# Power.net
KiCad netlist of a schematic drawn in Altium Designer
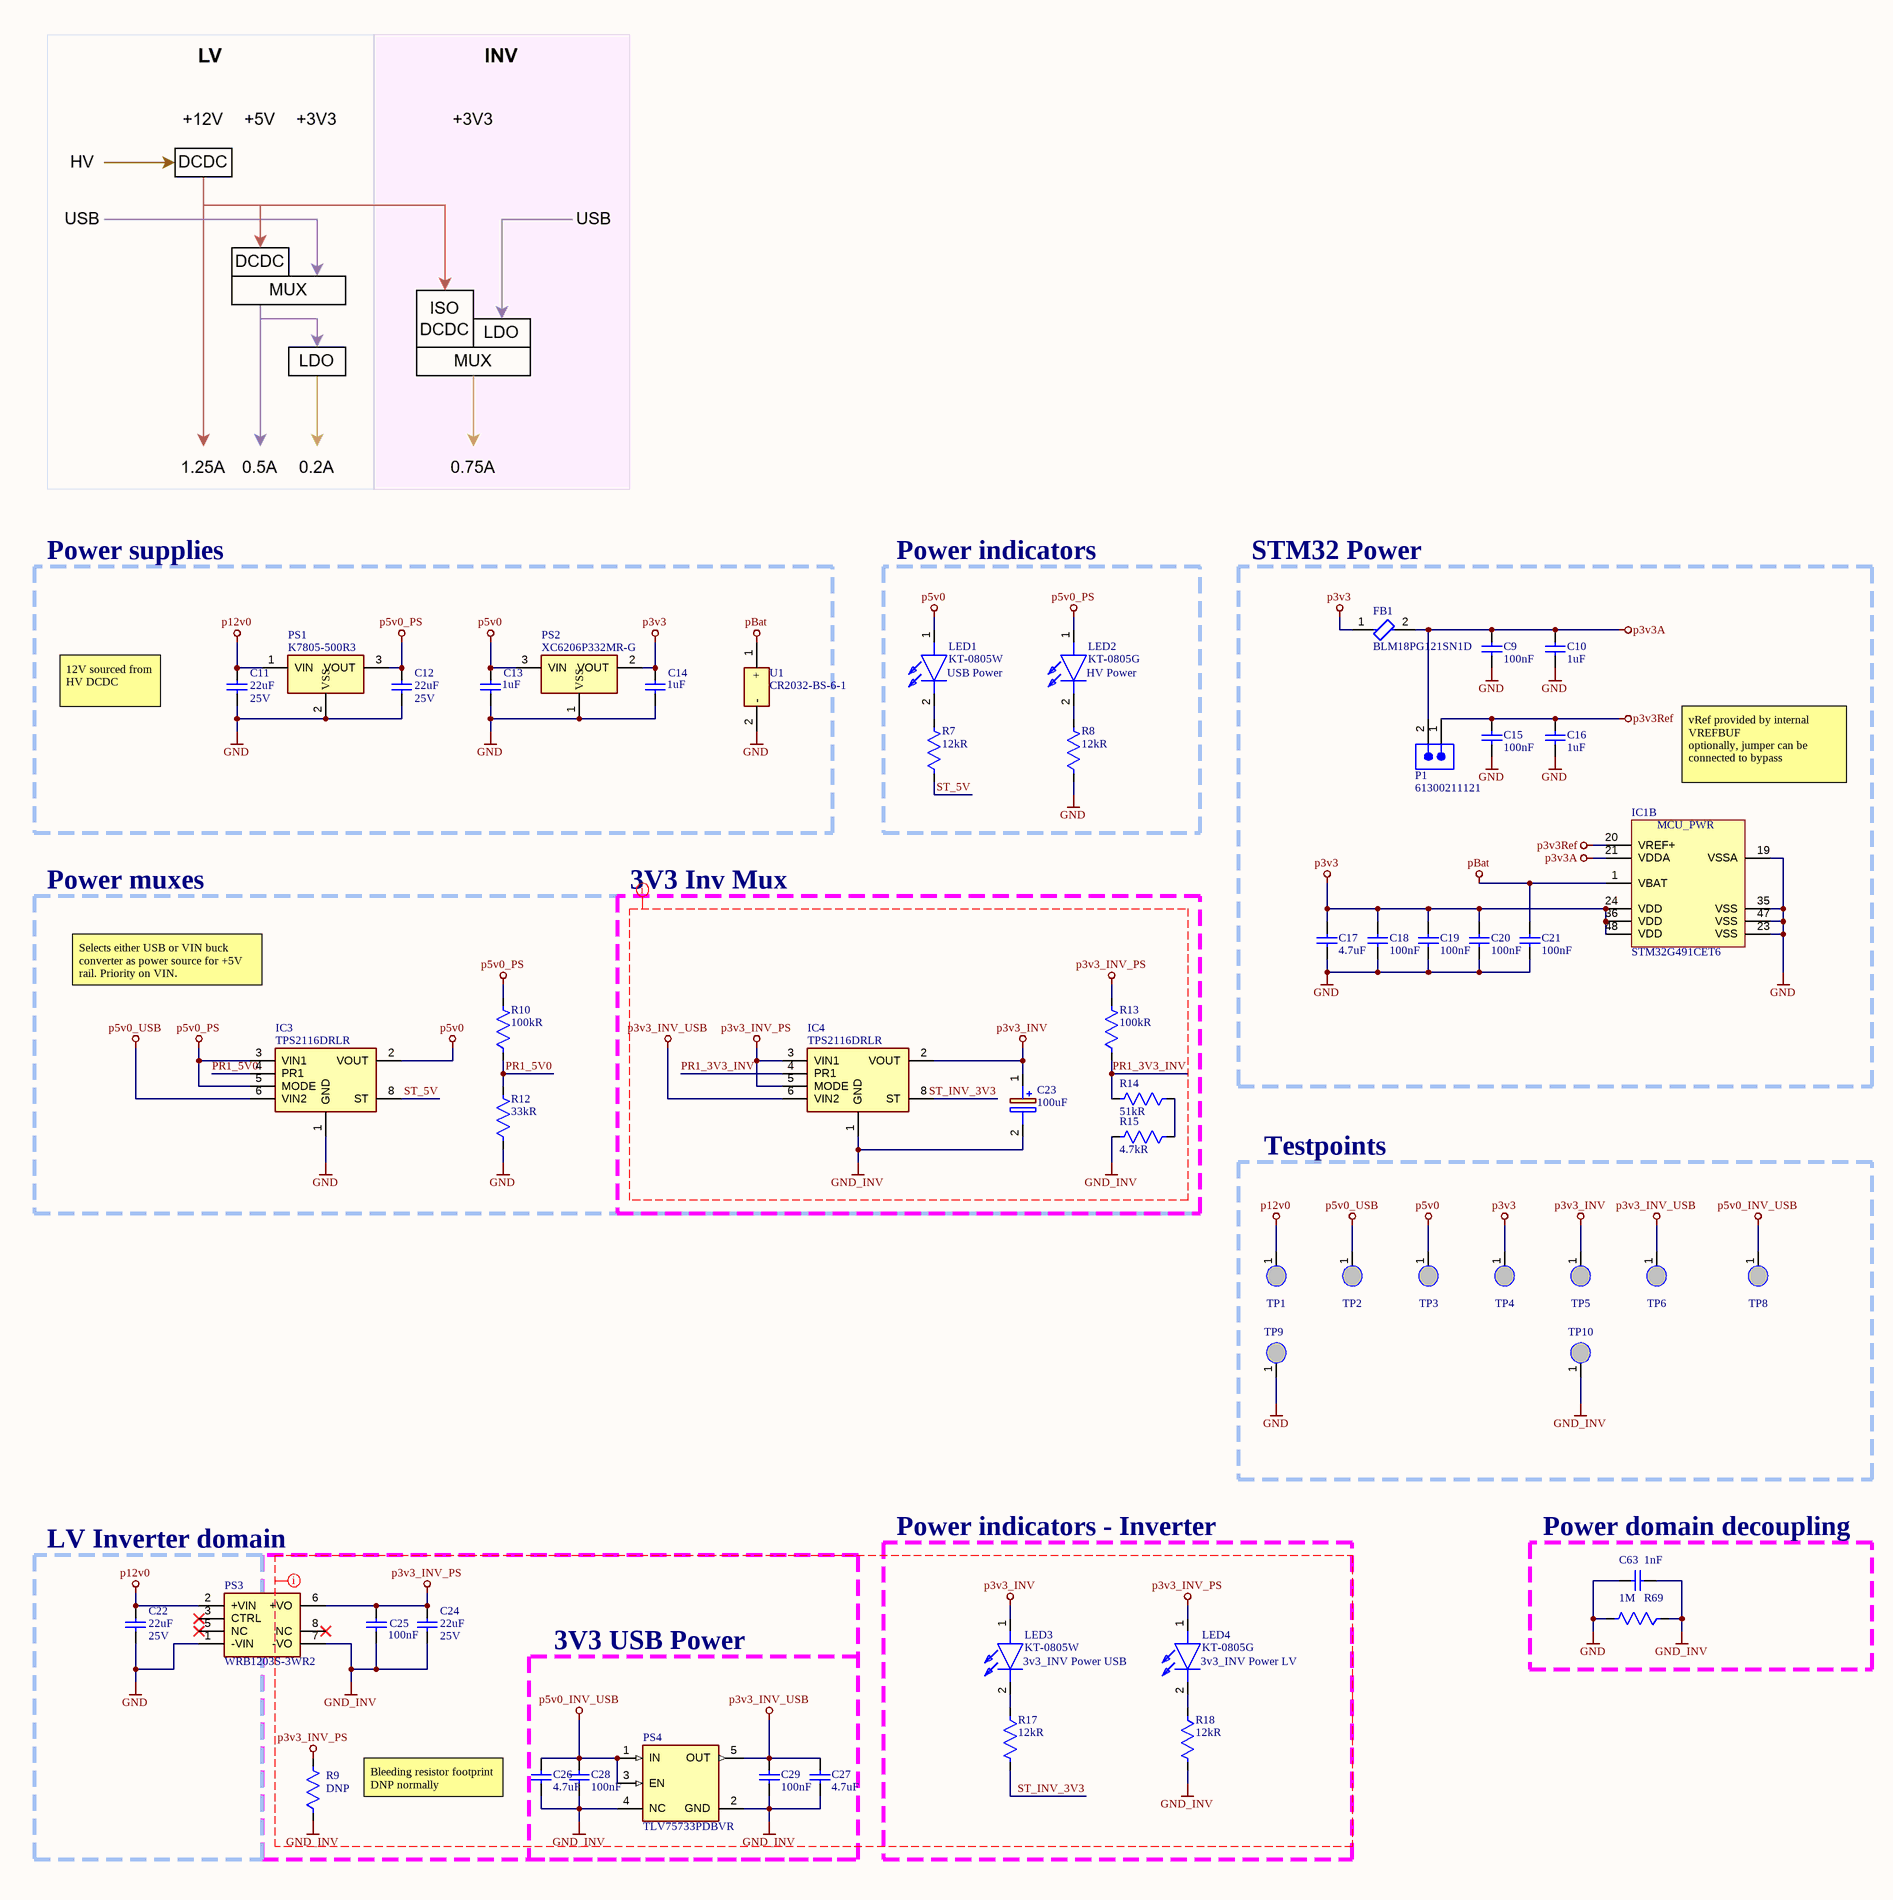
[diagram p0: Power.SchDoc, left]
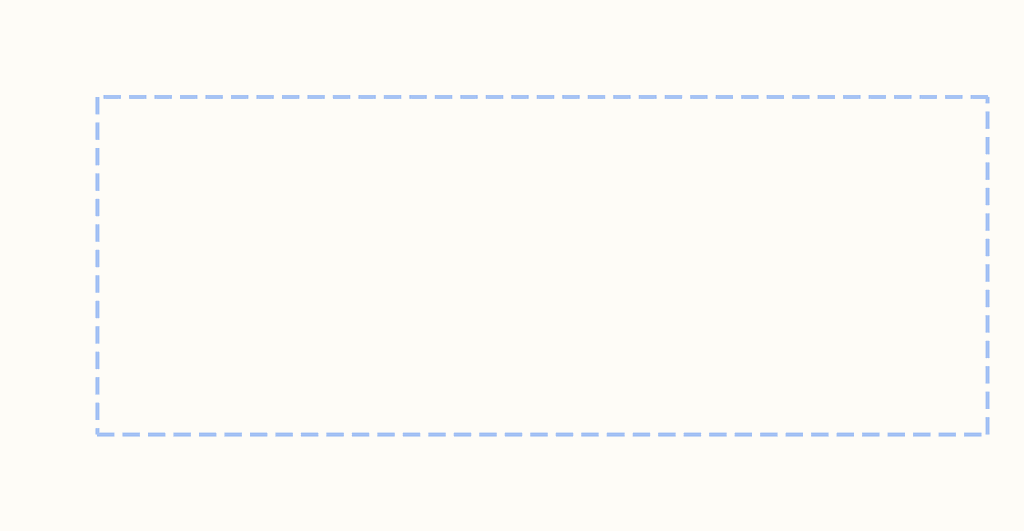
[diagram p1: Power.SchDoc, right]

(export (version "E")
  (design (tool "Eeschema 10.0.6"))
  (components
    (comp (ref "C9")
      (value "100nF")
      (footprint "WCAP-CSGP_0402_L1W0.5H0.5")
      (description "GTT Standard 0402 non-polarized capacitor")
      (fields (field (name "JLCPCB PART #") "C1525") (field (name "Comment") "CAP 0402 100nF X7R"))
      (libsource (lib "Green Team Twente") (part "CAP_NONPOL_GENERIC"))
    )
    (comp (ref "C10")
      (value "1uF")
      (footprint "WCAP-CSGP_0603_L1.6W0.8H0.8_Reflow")
      (description "GTT Standard 0603 non-polarized capacitor")
      (fields (field (name "JLCPCB PART #") "C15849") (field (name "Comment") "CAP 0603 1uF X7R"))
      (libsource (lib "Green Team Twente") (part "CAP_NONPOL_GENERIC"))
    )
    (comp (ref "C11")
      (value "22uF")
      (footprint "WCAP-CSGP_1206_L3.2W1.6H1.15")
      (description "GTT Standard 1206 non-polarized capacitor")
      (fields
        (field (name "VOLTAGE RATING") "25V")
        (field (name "JLCPCB PART #") "C12891")
        (field (name "Comment") "CAP 1206 22uF X7R")
      )
      (libsource (lib "Green Team Twente") (part "CAP_NONPOL_GENERIC"))
    )
    (comp (ref "C12")
      (value "22uF")
      (footprint "WCAP-CSGP_1206_L3.2W1.6H1.15")
      (description "GTT Standard 1206 non-polarized capacitor")
      (fields
        (field (name "VOLTAGE RATING") "25V")
        (field (name "JLCPCB PART #") "C12891")
        (field (name "Comment") "CAP 1206 22uF X7R")
      )
      (libsource (lib "Green Team Twente") (part "CAP_NONPOL_GENERIC"))
    )
    (comp (ref "C13")
      (value "1uF")
      (footprint "WCAP-CSGP_0603_L1.6W0.8H0.8_Reflow")
      (description "GTT Standard 0603 non-polarized capacitor")
      (fields (field (name "JLCPCB PART #") "C15849") (field (name "Comment") "CAP 0603 1uF X7R"))
      (libsource (lib "Green Team Twente") (part "CAP_NONPOL_GENERIC"))
    )
    (comp (ref "C14")
      (value "1uF")
      (footprint "WCAP-CSGP_0603_L1.6W0.8H0.8_Reflow")
      (description "GTT Standard 0603 non-polarized capacitor")
      (fields (field (name "JLCPCB PART #") "C15849") (field (name "Comment") "CAP 0603 1uF X7R"))
      (libsource (lib "Green Team Twente") (part "CAP_NONPOL_GENERIC"))
    )
    (comp (ref "C15")
      (value "100nF")
      (footprint "WCAP-CSGP_0402_L1W0.5H0.5")
      (description "GTT Standard 0402 non-polarized capacitor")
      (fields (field (name "JLCPCB PART #") "C1525") (field (name "Comment") "CAP 0402 100nF X7R"))
      (libsource (lib "Green Team Twente") (part "CAP_NONPOL_GENERIC"))
    )
    (comp (ref "C16")
      (value "1uF")
      (footprint "WCAP-CSGP_0603_L1.6W0.8H0.8_Reflow")
      (description "GTT Standard 0603 non-polarized capacitor")
      (fields (field (name "JLCPCB PART #") "C15849") (field (name "Comment") "CAP 0603 1uF X7R"))
      (libsource (lib "Green Team Twente") (part "CAP_NONPOL_GENERIC"))
    )
    (comp (ref "C17")
      (value "4.7uF")
      (footprint "WCAP-CSGP_0603_L1.6W0.8H0.8_Reflow")
      (description "GTT Standard 0603 non-polarized capacitor")
      (fields (field (name "JLCPCB PART #") "C19666") (field (name "Comment") "CAP 0603 4.7uF X7R"))
      (libsource (lib "Green Team Twente") (part "CAP_NONPOL_GENERIC"))
    )
    (comp (ref "C18")
      (value "100nF")
      (footprint "WCAP-CSGP_0402_L1W0.5H0.5")
      (description "GTT Standard 0402 non-polarized capacitor")
      (fields (field (name "JLCPCB PART #") "C1525") (field (name "Comment") "CAP 0402 100nF X7R"))
      (libsource (lib "Green Team Twente") (part "CAP_NONPOL_GENERIC"))
    )
    (comp (ref "C19")
      (value "100nF")
      (footprint "WCAP-CSGP_0402_L1W0.5H0.5")
      (description "GTT Standard 0402 non-polarized capacitor")
      (fields (field (name "JLCPCB PART #") "C1525") (field (name "Comment") "CAP 0402 100nF X7R"))
      (libsource (lib "Green Team Twente") (part "CAP_NONPOL_GENERIC"))
    )
    (comp (ref "C20")
      (value "100nF")
      (footprint "WCAP-CSGP_0402_L1W0.5H0.5")
      (description "GTT Standard 0402 non-polarized capacitor")
      (fields (field (name "JLCPCB PART #") "C1525") (field (name "Comment") "CAP 0402 100nF X7R"))
      (libsource (lib "Green Team Twente") (part "CAP_NONPOL_GENERIC"))
    )
    (comp (ref "C21")
      (value "100nF")
      (footprint "WCAP-CSGP_0402_L1W0.5H0.5")
      (description "GTT Standard 0402 non-polarized capacitor")
      (fields (field (name "JLCPCB PART #") "C1525") (field (name "Comment") "CAP 0402 100nF X7R"))
      (libsource (lib "Green Team Twente") (part "CAP_NONPOL_GENERIC"))
    )
    (comp (ref "C22")
      (value "22uF")
      (footprint "WCAP-CSGP_1206_L3.2W1.6H1.15")
      (description "GTT Standard 1206 non-polarized capacitor")
      (fields
        (field (name "VOLTAGE RATING") "25V")
        (field (name "JLCPCB PART #") "C12891")
        (field (name "Comment") "CAP 1206 22uF X7R")
      )
      (libsource (lib "Green Team Twente") (part "CAP_NONPOL_GENERIC"))
    )
    (comp (ref "C23")
      (value "100uF")
      (footprint "CAPAE660X800N")
      (description "Capacitor Polarised")
      (fields
        (field (name "MANUFACTURER_PART_NUMBER") "VEJ101M1ETR-0607")
        (field (name "JLCPCB PART #") "C176664")
      )
      (libsource (lib "FlexBMS_lib") (part "VEJ101M1ETR-0607"))
    )
    (comp (ref "C24")
      (value "22uF")
      (footprint "WCAP-CSGP_1206_L3.2W1.6H1.15")
      (description "GTT Standard 1206 non-polarized capacitor")
      (fields
        (field (name "VOLTAGE RATING") "25V")
        (field (name "JLCPCB PART #") "C12891")
        (field (name "Comment") "CAP 1206 22uF X7R")
      )
      (libsource (lib "Green Team Twente") (part "CAP_NONPOL_GENERIC"))
    )
    (comp (ref "C25")
      (value "100nF")
      (footprint "WCAP-CSGP_0402_L1W0.5H0.5")
      (description "GTT Standard 0402 non-polarized capacitor")
      (fields (field (name "JLCPCB PART #") "C1525") (field (name "Comment") "CAP 0402 100nF X7R"))
      (libsource (lib "Green Team Twente") (part "CAP_NONPOL_GENERIC"))
    )
    (comp (ref "C26")
      (value "4.7uF")
      (footprint "WCAP-CSGP_0603_L1.6W0.8H0.8_Reflow")
      (description "GTT Standard 0603 non-polarized capacitor")
      (fields (field (name "JLCPCB PART #") "C19666") (field (name "Comment") "CAP 0603 4.7uF X5R"))
      (libsource (lib "Green Team Twente") (part "CAP_NONPOL_GENERIC"))
    )
    (comp (ref "C27")
      (value "4.7uF")
      (footprint "WCAP-CSGP_0603_L1.6W0.8H0.8_Reflow")
      (description "GTT Standard 0603 non-polarized capacitor")
      (fields (field (name "JLCPCB PART #") "C19666") (field (name "Comment") "CAP 0603 4.7uF X5R"))
      (libsource (lib "Green Team Twente") (part "CAP_NONPOL_GENERIC"))
    )
    (comp (ref "C28")
      (value "100nF")
      (footprint "WCAP-CSGP_0402_L1W0.5H0.5")
      (description "GTT Standard 0402 non-polarized capacitor")
      (fields (field (name "JLCPCB PART #") "C1525") (field (name "Comment") "CAP 0402 100nF X7R"))
      (libsource (lib "Green Team Twente") (part "CAP_NONPOL_GENERIC"))
    )
    (comp (ref "C29")
      (value "100nF")
      (footprint "WCAP-CSGP_0402_L1W0.5H0.5")
      (description "GTT Standard 0402 non-polarized capacitor")
      (fields (field (name "JLCPCB PART #") "C1525") (field (name "Comment") "CAP 0402 100nF X7R"))
      (libsource (lib "Green Team Twente") (part "CAP_NONPOL_GENERIC"))
    )
    (comp (ref "C63")
      (value "1nF")
      (footprint "WCAP-CSGP_1206_L3.2W1.6H1.15")
      (description "GTT Standard 1206 non-polarized capacitor")
      (fields (field (name "JLCPCB PART #") "C9196") (field (name "Comment") "CAP 1206 1nF X7R"))
      (libsource (lib "Green Team Twente") (part "CAP_NONPOL_GENERIC"))
    )
    (comp (ref "FB1")
      (value "BLM18PG121SN1D")
      (footprint "FP-BLM18-0_15-t0_8-IPC_A")
      (description "Chip Ferrite Bead, 0603, 120Ω @ 100MHz, 0.05Ω, 25%, 2A")
      (fields (field (name "TOLERANCE") "25%"))
      (libsource (lib "Altium Content Vault") (part "5f30dd21d616792df468990f7003faa"))
    )
    (comp (ref "IC1")
      (value "STM32G491CET6")
      (footprint "QFP50P900X900X160-48N")
      (description "ARM Microcontrollers - MCU Mainstream Arm Cortex-M4+ MCU 170MHz with 512Kbytes of Flash memory")
      (fields (field (name "MOUSER PART NUMBER") "511-STM32G491CET6"))
      (libsource (lib "Green Team Twente") (part "STM32G491CET6"))
    )
    (comp (ref "IC3")
      (value "TPS2116DRLR")
      (footprint "SOTFL50P160X60-8N")
      (description "Power MUX")
      (fields (field (name "MOUSER PART NUMBER") "595-TPS2116DRLR"))
      (libsource (lib "Green Team Twente") (part "TPS2116DRLR"))
    )
    (comp (ref "IC4")
      (value "TPS2116DRLR")
      (footprint "SOTFL50P160X60-8N")
      (description "Power MUX")
      (fields (field (name "MOUSER PART NUMBER") "595-TPS2116DRLR"))
      (libsource (lib "Green Team Twente") (part "TPS2116DRLR"))
    )
    (comp (ref "LED1")
      (value "KT-0805W")
      (footprint "KT0805G")
      (description "LED")
      (fields (field (name "MANUFACTURER_PART_NUMBER") "KT-0805G") (field (name "JLCPCB PART #") "C34499"))
      (libsource (lib "FlexBMS_lib") (part "KT-0805G"))
    )
    (comp (ref "LED2")
      (value "KT-0805G")
      (footprint "KT0805G")
      (description "LED")
      (fields (field (name "JLCPCB PART #") "C2297"))
      (libsource (lib "FlexBMS_lib") (part "KT-0805G"))
    )
    (comp (ref "LED3")
      (value "KT-0805W")
      (footprint "KT0805G")
      (description "LED")
      (fields (field (name "MANUFACTURER_PART_NUMBER") "KT-0805G") (field (name "JLCPCB PART #") "C34499"))
      (libsource (lib "FlexBMS_lib") (part "KT-0805G"))
    )
    (comp (ref "LED4")
      (value "KT-0805G")
      (footprint "KT0805G")
      (description "LED")
      (fields (field (name "JLCPCB PART #") "C2297"))
      (libsource (lib "FlexBMS_lib") (part "KT-0805G"))
    )
    (comp (ref "P1")
      (value "61300211121")
      (footprint "61300211121")
      (description "WR-PHD Pin Header, THT, Vertical, pitch 2.54mm, 1 Row, 2P")
      (fields (field (name "MANUFACTURER") "Wurth Elektronik"))
      (libsource (lib "Green Team Twente") (part "62000211121"))
    )
    (comp (ref "PS1")
      (value "K7805-500R3")
      (footprint "K7805500R3")
      (description "Power Supply")
      (fields (field (name "JLCPCB PART #") "C19188491"))
      (libsource (lib "FlexBMS_lib") (part "K7805-500R3"))
    )
    (comp (ref "PS2")
      (value "XC6206P332MR-G")
      (footprint "SOT95P280X130-3N")
      (description "Power Supply")
      (fields (field (name "MOUSER PART NUMBER") "865-XC6206P332MR-G"))
      (libsource (lib "FlexBMS_lib") (part "XC6206P332MR-G"))
    )
    (comp (ref "PS3")
      (value "WRB1203S-3WR2")
      (footprint "WRB1203S3WR2")
      (description "Power Supply")
      (fields (field (name "JLCPCB PART #") "C22437321"))
      (libsource (lib "FlexBMS_lib") (part "WRB1203S-3WR2"))
    )
    (comp (ref "PS4")
      (value "TLV75733PDBVR")
      (footprint "FP-DBV0005A-MFG")
      (description "IC REG LINEAR 3.3V 1A SOT23-5")
      (fields
        (field (name "MANUFACTURER") "Texas Instruments")
        (field (name "OCTOPART") "https://octopart.com/tlv75733pdbvr-texas+instruments-91437073")
      )
      (libsource (lib "Altium Content Vault") (part "0cbbc1df71e5372cce39b1d408f1f92"))
    )
    (comp (ref "R7")
      (value "12kR")
      (footprint "FP0402")
      (description "GTT Standard 0402 Resistor")
      (fields (field (name "TOLERANCE") "1%") (field (name "POWER") "62.5mW"))
      (libsource (lib "Green Team Twente") (part "RES_GENERIC"))
    )
    (comp (ref "R8")
      (value "12kR")
      (footprint "FP0402")
      (description "GTT Standard 0402 Resistor")
      (fields (field (name "TOLERANCE") "1%") (field (name "POWER") "62.5mW"))
      (libsource (lib "Green Team Twente") (part "RES_GENERIC"))
    )
    (comp (ref "R9")
      (value "DNP")
      (footprint "RES_SM1206_YAGEORC_N")
      (description "GTT Standard 1206 Resistor")
      (fields (field (name "TOLERANCE") "1%") (field (name "POWER") "62.5mW"))
      (libsource (lib "Green Team Twente") (part "RES_GENERIC"))
    )
    (comp (ref "R10")
      (value "100kR")
      (footprint "FP0402")
      (description "GTT Standard 0402 Resistor")
      (fields (field (name "TOLERANCE") "1%") (field (name "POWER") "62.5mW"))
      (libsource (lib "Green Team Twente") (part "RES_GENERIC"))
    )
    (comp (ref "R12")
      (value "33kR")
      (footprint "FP0402")
      (description "GTT Standard 0402 Resistor")
      (fields (field (name "TOLERANCE") "1%") (field (name "POWER") "62.5mW"))
      (libsource (lib "Green Team Twente") (part "RES_GENERIC"))
    )
    (comp (ref "R13")
      (value "100kR")
      (footprint "FP0402")
      (description "GTT Standard 0402 Resistor")
      (fields (field (name "TOLERANCE") "1%") (field (name "POWER") "62.5mW"))
      (libsource (lib "Green Team Twente") (part "RES_GENERIC"))
    )
    (comp (ref "R14")
      (value "51kR")
      (footprint "FP0402")
      (description "GTT Standard 0402 Resistor")
      (fields (field (name "TOLERANCE") "1%") (field (name "POWER") "62.5mW"))
      (libsource (lib "Green Team Twente") (part "RES_GENERIC"))
    )
    (comp (ref "R15")
      (value "4.7kR")
      (footprint "FP0402")
      (description "GTT Standard 0402 Resistor")
      (fields (field (name "TOLERANCE") "1%") (field (name "POWER") "62.5mW"))
      (libsource (lib "Green Team Twente") (part "RES_GENERIC"))
    )
    (comp (ref "R17")
      (value "12kR")
      (footprint "RES_SM0603_YAGEORC_N")
      (description "GTT Standard 0603 Resistor")
      (fields (field (name "POWER") "62.5mW") (field (name "TOLERANCE") "1%"))
      (libsource (lib "Green Team Twente") (part "RES_GENERIC"))
    )
    (comp (ref "R18")
      (value "12kR")
      (footprint "RES_SM0603_YAGEORC_N")
      (description "GTT Standard 0603 Resistor")
      (fields (field (name "POWER") "62.5mW") (field (name "TOLERANCE") "1%"))
      (libsource (lib "Green Team Twente") (part "RES_GENERIC"))
    )
    (comp (ref "R69")
      (value "1M")
      (footprint "RES_SM1206_YAGEORC_N")
      (description "GTT Standard 1206 Resistor")
      (fields (field (name "TOLERANCE") "1%") (field (name "POWER") "62.5mW"))
      (libsource (lib "Green Team Twente") (part "RES_GENERIC"))
    )
    (comp (ref "TP1")
      (value "GTT_ProbeerPunt")
      (footprint "GTT_ProbeerPuntFP")
      (libsource (lib "Green Team Twente") (part "Test Point"))
    )
    (comp (ref "TP2")
      (value "GTT_ProbeerPunt")
      (footprint "GTT_ProbeerPuntFP")
      (libsource (lib "Green Team Twente") (part "Test Point"))
    )
    (comp (ref "TP3")
      (value "GTT_ProbeerPunt")
      (footprint "GTT_ProbeerPuntFP")
      (libsource (lib "Green Team Twente") (part "Test Point"))
    )
    (comp (ref "TP4")
      (value "GTT_ProbeerPunt")
      (footprint "GTT_ProbeerPuntFP")
      (libsource (lib "Green Team Twente") (part "Test Point"))
    )
    (comp (ref "TP5")
      (value "GTT_ProbeerPunt")
      (footprint "GTT_ProbeerPuntFP")
      (libsource (lib "Green Team Twente") (part "Test Point"))
    )
    (comp (ref "TP6")
      (value "GTT_ProbeerPunt")
      (footprint "GTT_ProbeerPuntFP")
      (libsource (lib "Green Team Twente") (part "Test Point"))
    )
    (comp (ref "TP8")
      (value "GTT_ProbeerPunt")
      (footprint "GTT_ProbeerPuntFP")
      (libsource (lib "Green Team Twente") (part "Test Point"))
    )
    (comp (ref "TP9")
      (value "GTT_ProbeerPunt")
      (footprint "GTT_ProbeerPuntFP")
      (libsource (lib "Green Team Twente") (part "Test Point"))
    )
    (comp (ref "TP10")
      (value "GTT_ProbeerPunt")
      (footprint "GTT_ProbeerPuntFP")
      (libsource (lib "Green Team Twente") (part "Test Point"))
    )
    (comp (ref "U1")
      (value "CR2032-BS-6-1")
      (footprint "CR2032BS61")
      (description "Undefined or Miscellaneous")
      (libsource (lib "FlexBMS_lib") (part "CR2032-BS-6-1"))
    )
  )
  (nets
    (net (code "1") (name "/PR1_3V3_INV") (class "Default")
      (node (ref "IC4") (pin "4") (pinfunction "PR1_4") (pintype "passive"))
      (node (ref "R13") (pin "1") (pinfunction "1_1") (pintype "passive"))
      (node (ref "R14") (pin "2") (pinfunction "2_2") (pintype "passive"))
    )
    (net (code "2") (name "/PR1_5V0") (class "Default")
      (node (ref "IC3") (pin "4") (pinfunction "PR1_4") (pintype "passive"))
      (node (ref "R10") (pin "1") (pinfunction "1_1") (pintype "passive"))
      (node (ref "R12") (pin "2") (pinfunction "2_2") (pintype "passive"))
    )
    (net (code "3") (name "/ST_5V") (class "Default")
      (node (ref "IC3") (pin "8") (pinfunction "ST_8") (pintype "passive"))
      (node (ref "R7") (pin "1") (pinfunction "1_1") (pintype "passive"))
    )
    (net (code "4") (name "/ST_INV_3V3") (class "Default")
      (node (ref "IC4") (pin "8") (pinfunction "ST_8") (pintype "passive"))
      (node (ref "R17") (pin "2") (pinfunction "2_2") (pintype "passive"))
    )
    (net (code "5") (name "GND") (class "Default")
      (node (ref "C10") (pin "2") (pinfunction "2_2") (pintype "passive"))
      (node (ref "C11") (pin "1") (pinfunction "1_1") (pintype "passive"))
      (node (ref "C12") (pin "1") (pinfunction "1_1") (pintype "passive"))
      (node (ref "C13") (pin "1") (pinfunction "1_1") (pintype "passive"))
      (node (ref "C14") (pin "1") (pinfunction "1_1") (pintype "passive"))
      (node (ref "C15") (pin "1") (pinfunction "1_1") (pintype "passive"))
      (node (ref "C16") (pin "2") (pinfunction "2_2") (pintype "passive"))
      (node (ref "C17") (pin "2") (pinfunction "2_2") (pintype "passive"))
      (node (ref "C18") (pin "1") (pinfunction "1_1") (pintype "passive"))
      (node (ref "C19") (pin "1") (pinfunction "1_1") (pintype "passive"))
      (node (ref "C20") (pin "1") (pinfunction "1_1") (pintype "passive"))
      (node (ref "C21") (pin "1") (pinfunction "1_1") (pintype "passive"))
      (node (ref "C22") (pin "1") (pinfunction "1_1") (pintype "passive"))
      (node (ref "C63") (pin "1") (pinfunction "1_1") (pintype "passive"))
      (node (ref "C9") (pin "1") (pinfunction "1_1") (pintype "passive"))
      (node (ref "IC1") (pin "19") (pinfunction "VSSA_19") (pintype "passive"))
      (node (ref "IC1") (pin "23") (pinfunction "VSS_23") (pintype "passive"))
      (node (ref "IC1") (pin "35") (pinfunction "VSS_35") (pintype "passive"))
      (node (ref "IC1") (pin "47") (pinfunction "VSS_47") (pintype "passive"))
      (node (ref "IC3") (pin "1") (pinfunction "GND_1") (pintype "passive"))
      (node (ref "PS1") (pin "2") (pinfunction "VSS_2") (pintype "passive"))
      (node (ref "PS2") (pin "1") (pinfunction "VSS_1") (pintype "power_in"))
      (node (ref "PS3") (pin "1") (pinfunction "-VIN_1") (pintype "passive"))
      (node (ref "R12") (pin "1") (pinfunction "1_1") (pintype "passive"))
      (node (ref "R69") (pin "2") (pinfunction "2_2") (pintype "passive"))
      (node (ref "R8") (pin "1") (pinfunction "1_1") (pintype "passive"))
      (node (ref "TP9") (pin "1") (pinfunction "1_1") (pintype "passive"))
      (node (ref "U1") (pin "2") (pinfunction "-_2") (pintype "passive"))
    )
    (net (code "6") (name "GND_INV") (class "Default")
      (node (ref "C23") (pin "2") (pinfunction "-_2") (pintype "passive"))
      (node (ref "C24") (pin "1") (pinfunction "1_1") (pintype "passive"))
      (node (ref "C25") (pin "1") (pinfunction "1_1") (pintype "passive"))
      (node (ref "C26") (pin "2") (pinfunction "2_2") (pintype "passive"))
      (node (ref "C27") (pin "2") (pinfunction "2_2") (pintype "passive"))
      (node (ref "C28") (pin "1") (pinfunction "1_1") (pintype "passive"))
      (node (ref "C29") (pin "1") (pinfunction "1_1") (pintype "passive"))
      (node (ref "C63") (pin "2") (pinfunction "2_2") (pintype "passive"))
      (node (ref "IC4") (pin "1") (pinfunction "GND_1") (pintype "passive"))
      (node (ref "PS3") (pin "7") (pinfunction "-VO_7") (pintype "passive"))
      (node (ref "PS4") (pin "2") (pinfunction "GND_2") (pintype "power_in"))
      (node (ref "PS4") (pin "4") (pinfunction "NC_4") (pintype "passive"))
      (node (ref "R15") (pin "2") (pinfunction "2_2") (pintype "passive"))
      (node (ref "R18") (pin "2") (pinfunction "2_2") (pintype "passive"))
      (node (ref "R69") (pin "1") (pinfunction "1_1") (pintype "passive"))
      (node (ref "R9") (pin "1") (pinfunction "1_1") (pintype "passive"))
      (node (ref "TP10") (pin "1") (pinfunction "1_1") (pintype "passive"))
    )
    (net (code "7") (name "Net-(LED1-K)") (class "Default")
      (node (ref "LED1") (pin "2") (pinfunction "K_2") (pintype "passive"))
      (node (ref "R7") (pin "2") (pinfunction "2_2") (pintype "passive"))
    )
    (net (code "8") (name "Net-(LED2-K)") (class "Default")
      (node (ref "LED2") (pin "2") (pinfunction "K_2") (pintype "passive"))
      (node (ref "R8") (pin "2") (pinfunction "2_2") (pintype "passive"))
    )
    (net (code "9") (name "Net-(LED3-K)") (class "Default")
      (node (ref "LED3") (pin "2") (pinfunction "K_2") (pintype "passive"))
      (node (ref "R17") (pin "1") (pinfunction "1_1") (pintype "passive"))
    )
    (net (code "10") (name "Net-(LED4-K)") (class "Default")
      (node (ref "LED4") (pin "2") (pinfunction "K_2") (pintype "passive"))
      (node (ref "R18") (pin "1") (pinfunction "1_1") (pintype "passive"))
    )
    (net (code "11") (name "Net-(R14-Pad1)") (class "Default")
      (node (ref "R14") (pin "1") (pinfunction "1_1") (pintype "passive"))
      (node (ref "R15") (pin "1") (pinfunction "1_1") (pintype "passive"))
    )
    (net (code "12") (name "p3v3") (class "Default")
      (node (ref "C14") (pin "2") (pinfunction "2_2") (pintype "passive"))
      (node (ref "C17") (pin "1") (pinfunction "1_1") (pintype "passive"))
      (node (ref "C18") (pin "2") (pinfunction "2_2") (pintype "passive"))
      (node (ref "C19") (pin "2") (pinfunction "2_2") (pintype "passive"))
      (node (ref "C20") (pin "2") (pinfunction "2_2") (pintype "passive"))
      (node (ref "FB1") (pin "1") (pinfunction "1_1") (pintype "passive"))
      (node (ref "IC1") (pin "24") (pinfunction "VDD_24") (pintype "passive"))
      (node (ref "IC1") (pin "36") (pinfunction "VDD_36") (pintype "passive"))
      (node (ref "IC1") (pin "48") (pinfunction "VDD_48") (pintype "passive"))
      (node (ref "PS2") (pin "2") (pinfunction "VOUT_2") (pintype "power_in"))
      (node (ref "TP4") (pin "1") (pinfunction "1_1") (pintype "passive"))
    )
    (net (code "13") (name "p3v3A") (class "Default")
      (node (ref "C10") (pin "1") (pinfunction "1_1") (pintype "passive"))
      (node (ref "C9") (pin "2") (pinfunction "2_2") (pintype "passive"))
      (node (ref "FB1") (pin "2") (pinfunction "2_2") (pintype "passive"))
      (node (ref "IC1") (pin "21") (pinfunction "VDDA_21") (pintype "passive"))
      (node (ref "P1") (pin "2") (pinfunction "2_2") (pintype "passive"))
    )
    (net (code "14") (name "p3v3Ref") (class "Default")
      (node (ref "C15") (pin "2") (pinfunction "2_2") (pintype "passive"))
      (node (ref "C16") (pin "1") (pinfunction "1_1") (pintype "passive"))
      (node (ref "IC1") (pin "20") (pinfunction "VREF+_20") (pintype "passive"))
      (node (ref "P1") (pin "1") (pinfunction "1_1") (pintype "passive"))
    )
    (net (code "15") (name "p3v3_INV") (class "Default")
      (node (ref "C23") (pin "1") (pinfunction "+_1") (pintype "passive"))
      (node (ref "IC4") (pin "2") (pinfunction "VOUT_2") (pintype "passive"))
      (node (ref "LED3") (pin "1") (pinfunction "A_1") (pintype "passive"))
      (node (ref "TP5") (pin "1") (pinfunction "1_1") (pintype "passive"))
    )
    (net (code "16") (name "p3v3_INV_PS") (class "Default")
      (node (ref "C24") (pin "2") (pinfunction "2_2") (pintype "passive"))
      (node (ref "C25") (pin "2") (pinfunction "2_2") (pintype "passive"))
      (node (ref "IC4") (pin "3") (pinfunction "VIN1_3") (pintype "passive"))
      (node (ref "IC4") (pin "5") (pinfunction "MODE_5") (pintype "passive"))
      (node (ref "LED4") (pin "1") (pinfunction "A_1") (pintype "passive"))
      (node (ref "PS3") (pin "6") (pinfunction "+VO_6") (pintype "passive"))
      (node (ref "R13") (pin "2") (pinfunction "2_2") (pintype "passive"))
      (node (ref "R9") (pin "2") (pinfunction "2_2") (pintype "passive"))
    )
    (net (code "17") (name "p3v3_INV_USB") (class "Default")
      (node (ref "C27") (pin "1") (pinfunction "1_1") (pintype "passive"))
      (node (ref "C29") (pin "2") (pinfunction "2_2") (pintype "passive"))
      (node (ref "IC4") (pin "6") (pinfunction "VIN2_6") (pintype "passive"))
      (node (ref "PS4") (pin "5") (pinfunction "OUT_5") (pintype "output"))
      (node (ref "TP6") (pin "1") (pinfunction "1_1") (pintype "passive"))
    )
    (net (code "18") (name "p5v0") (class "Default")
      (node (ref "C13") (pin "2") (pinfunction "2_2") (pintype "passive"))
      (node (ref "IC3") (pin "2") (pinfunction "VOUT_2") (pintype "passive"))
      (node (ref "LED1") (pin "1") (pinfunction "A_1") (pintype "passive"))
      (node (ref "PS2") (pin "3") (pinfunction "VIN_3") (pintype "power_in"))
      (node (ref "TP3") (pin "1") (pinfunction "1_1") (pintype "passive"))
    )
    (net (code "19") (name "p5v0_INV_USB") (class "Default")
      (node (ref "C26") (pin "1") (pinfunction "1_1") (pintype "passive"))
      (node (ref "C28") (pin "2") (pinfunction "2_2") (pintype "passive"))
      (node (ref "PS4") (pin "1") (pinfunction "IN_1") (pintype "input"))
      (node (ref "PS4") (pin "3") (pinfunction "EN_3") (pintype "input"))
      (node (ref "TP8") (pin "1") (pinfunction "1_1") (pintype "passive"))
    )
    (net (code "20") (name "p5v0_PS") (class "Default")
      (node (ref "C12") (pin "2") (pinfunction "2_2") (pintype "passive"))
      (node (ref "IC3") (pin "3") (pinfunction "VIN1_3") (pintype "passive"))
      (node (ref "IC3") (pin "5") (pinfunction "MODE_5") (pintype "passive"))
      (node (ref "LED2") (pin "1") (pinfunction "A_1") (pintype "passive"))
      (node (ref "PS1") (pin "3") (pinfunction "VOUT_3") (pintype "passive"))
      (node (ref "R10") (pin "2") (pinfunction "2_2") (pintype "passive"))
    )
    (net (code "21") (name "p5v0_USB") (class "Default")
      (node (ref "IC3") (pin "6") (pinfunction "VIN2_6") (pintype "passive"))
      (node (ref "TP2") (pin "1") (pinfunction "1_1") (pintype "passive"))
    )
    (net (code "22") (name "p12v0") (class "Default")
      (node (ref "C11") (pin "2") (pinfunction "2_2") (pintype "passive"))
      (node (ref "C22") (pin "2") (pinfunction "2_2") (pintype "passive"))
      (node (ref "PS1") (pin "1") (pinfunction "VIN_1") (pintype "passive"))
      (node (ref "PS3") (pin "2") (pinfunction "+VIN_2") (pintype "passive"))
      (node (ref "TP1") (pin "1") (pinfunction "1_1") (pintype "passive"))
    )
    (net (code "23") (name "pBat") (class "Default")
      (node (ref "C21") (pin "2") (pinfunction "2_2") (pintype "passive"))
      (node (ref "IC1") (pin "1") (pinfunction "VBAT_1") (pintype "passive"))
      (node (ref "U1") (pin "1") (pinfunction "+_1") (pintype "passive"))
    )
    (net (code "24") (name "unconnected-(PS3-CTRL-Pad3)") (class "Default")
      (node (ref "PS3") (pin "3") (pinfunction "CTRL_3") (pintype "passive+no_connect"))
    )
    (net (code "25") (name "unconnected-(PS3-NC-Pad5)") (class "Default")
      (node (ref "PS3") (pin "5") (pinfunction "NC_5") (pintype "passive+no_connect"))
    )
    (net (code "26") (name "unconnected-(PS3-NC-Pad8)") (class "Default")
      (node (ref "PS3") (pin "8") (pinfunction "NC_8") (pintype "passive+no_connect"))
    )
  )
)
